# Main_Flam.net
KiCad netlist of a schematic drawn in EAGLE
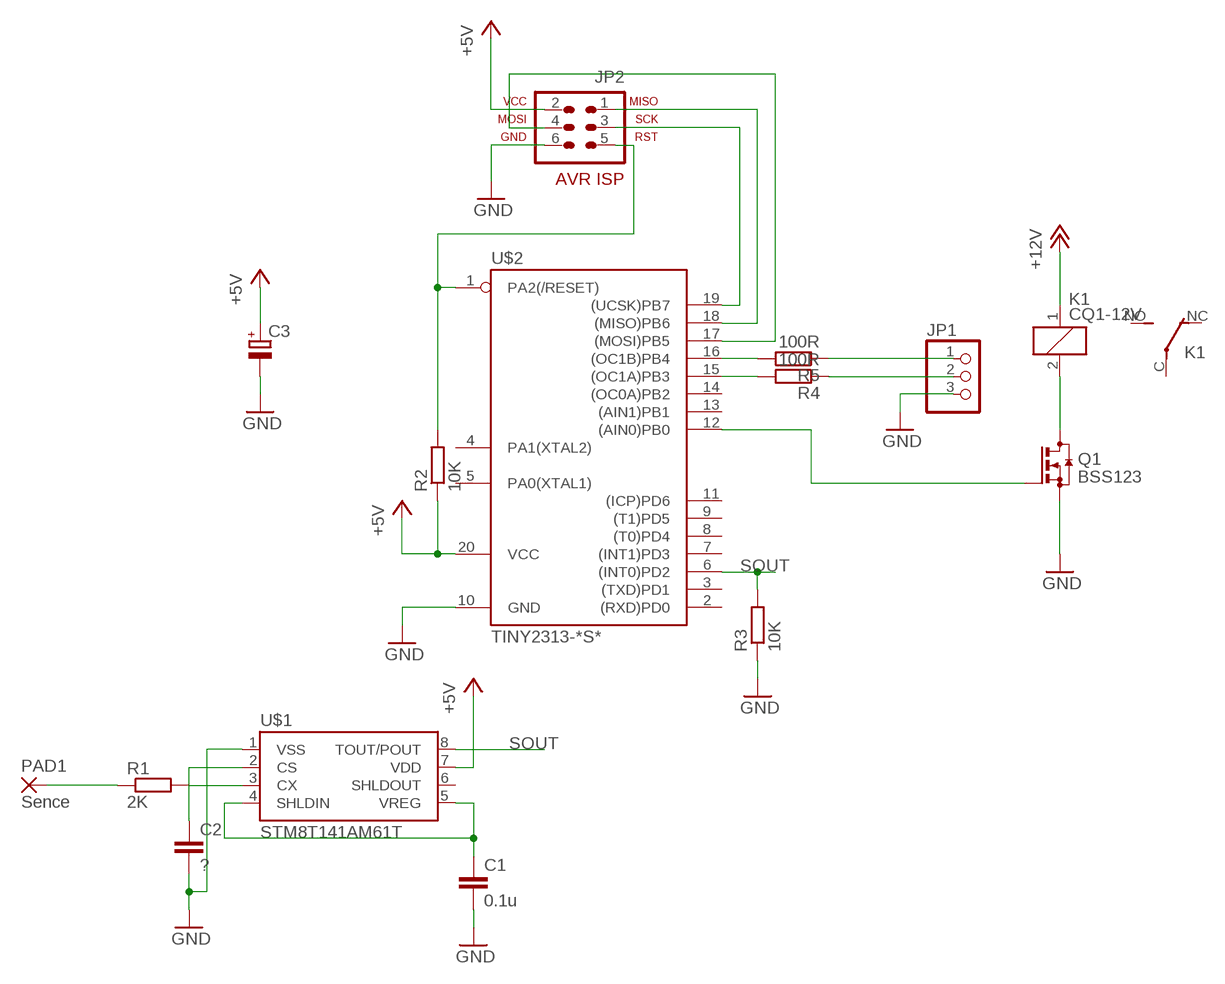
[diagram p0: schematic, sheet 1]

(export (version "E")
  (design (tool "Eeschema 10.0.6"))
  (components
    (comp (ref "C1")
      (value "0.1u")
      (footprint "eagle-import:C1206")
      (libsource (lib "eagle-import") (part "C-EUC1206"))
    )
    (comp (ref "C2")
      (value "?")
      (footprint "eagle-import:C1206")
      (libsource (lib "eagle-import") (part "C-EUC1206"))
    )
    (comp (ref "C3")
      (value "CPOL-EUSMCB")
      (footprint "eagle-import:SMC_B")
      (libsource (lib "eagle-import") (part "CPOL-EUSMCB"))
    )
    (comp (ref "JP1")
      (value "PINHD-1X3")
      (footprint "eagle-import:1X03")
      (libsource (lib "eagle-import") (part "PINHD-1X3"))
    )
    (comp (ref "JP2")
      (value "AVR-ISP-6VERT")
      (footprint "eagle-import:AVR-ISP-6")
      (libsource (lib "eagle-import") (part "AVR-ISP-6VERT"))
    )
    (comp (ref "K1")
      (value "CQ1-12V")
      (footprint "eagle-import:CQ1")
      (libsource (lib "eagle-import") (part "CQ1-12V"))
    )
    (comp (ref "PAD1")
      (value "Sence")
      (footprint "eagle-import:2,54_0,8")
      (libsource (lib "eagle-import") (part "2,54/0,8"))
    )
    (comp (ref "Q1")
      (value "BSS123")
      (footprint "eagle-import:SOT23")
      (libsource (lib "eagle-import") (part "BSS123"))
    )
    (comp (ref "R1")
      (value "2K")
      (footprint "eagle-import:R1206")
      (libsource (lib "eagle-import") (part "R-EU_R1206"))
    )
    (comp (ref "R2")
      (value "10K")
      (footprint "eagle-import:R1206")
      (libsource (lib "eagle-import") (part "R-EU_R1206"))
    )
    (comp (ref "R3")
      (value "10K")
      (footprint "eagle-import:R1206")
      (libsource (lib "eagle-import") (part "R-EU_R1206"))
    )
    (comp (ref "R4")
      (value "100R")
      (footprint "eagle-import:R1206")
      (libsource (lib "eagle-import") (part "R-EU_R1206"))
    )
    (comp (ref "R5")
      (value "100R")
      (footprint "eagle-import:R1206")
      (libsource (lib "eagle-import") (part "R-EU_R1206"))
    )
    (comp (ref "U$1")
      (value "STM8T141AM61T")
      (footprint "eagle-import:SO8")
      (libsource (lib "eagle-import") (part "STM8T141AM61T"))
    )
    (comp (ref "U$2")
      (value "TINY2313-*S*")
      (footprint "eagle-import:SO20L$")
      (libsource (lib "eagle-import") (part "TINY2313-S"))
    )
  )
  (nets
    (net (code "1") (name "+5V") (class "Default")
      (node (ref "C3") (pin "+") (pinfunction "+_+") (pintype "passive"))
      (node (ref "JP2") (pin "2") (pinfunction "2_2") (pintype "passive"))
      (node (ref "R2") (pin "1") (pinfunction "1_1") (pintype "passive"))
      (node (ref "U$1") (pin "7") (pinfunction "VDD_7") (pintype "bidirectional"))
      (node (ref "U$2") (pin "20") (pinfunction "VCC_20") (pintype "power_in"))
    )
    (net (code "2") (name "+12V") (class "Default")
      (node (ref "K1") (pin "1") (pinfunction "1_1") (pintype "passive"))
    )
    (net (code "3") (name "/SOUT") (class "Default")
      (node (ref "R3") (pin "2") (pinfunction "2_2") (pintype "passive"))
      (node (ref "U$1") (pin "8") (pinfunction "TOUT/POUT_8") (pintype "bidirectional"))
      (node (ref "U$2") (pin "6") (pinfunction "(INT0)PD2_6") (pintype "bidirectional"))
    )
    (net (code "4") (name "GND") (class "Default")
      (node (ref "C1") (pin "2") (pinfunction "2_2") (pintype "passive"))
      (node (ref "C2") (pin "2") (pinfunction "2_2") (pintype "passive"))
      (node (ref "C3") (pin "-") (pinfunction "-_-") (pintype "passive"))
      (node (ref "JP1") (pin "3") (pinfunction "3_3") (pintype "passive"))
      (node (ref "JP2") (pin "6") (pinfunction "6_6") (pintype "passive"))
      (node (ref "Q1") (pin "2") (pinfunction "S_2") (pintype "passive"))
      (node (ref "R3") (pin "1") (pinfunction "1_1") (pintype "passive"))
      (node (ref "U$1") (pin "1") (pinfunction "VSS_1") (pintype "bidirectional"))
      (node (ref "U$2") (pin "10") (pinfunction "GND_10") (pintype "power_in"))
    )
    (net (code "5") (name "Net-(JP1-Pad1)") (class "Default")
      (node (ref "JP1") (pin "1") (pinfunction "1_1") (pintype "passive"))
      (node (ref "R5") (pin "1") (pinfunction "1_1") (pintype "passive"))
    )
    (net (code "6") (name "Net-(JP1-Pad2)") (class "Default")
      (node (ref "JP1") (pin "2") (pinfunction "2_2") (pintype "passive"))
      (node (ref "R4") (pin "1") (pinfunction "1_1") (pintype "passive"))
    )
    (net (code "7") (name "Net-(PAD1-P)") (class "Default")
      (node (ref "PAD1") (pin "1") (pinfunction "P_1") (pintype "passive"))
      (node (ref "R1") (pin "1") (pinfunction "1_1") (pintype "passive"))
    )
    (net (code "8") (name "Net-(Q1-D)") (class "Default")
      (node (ref "K1") (pin "2") (pinfunction "2_2") (pintype "passive"))
      (node (ref "Q1") (pin "3") (pinfunction "D_3") (pintype "passive"))
    )
    (net (code "9") (name "Net-(Q1-G)") (class "Default")
      (node (ref "Q1") (pin "1") (pinfunction "G_1") (pintype "passive"))
      (node (ref "U$2") (pin "12") (pinfunction "(AIN0)PB0_12") (pintype "bidirectional"))
    )
    (net (code "10") (name "Net-(U$1-CS)") (class "Default")
      (node (ref "C2") (pin "1") (pinfunction "1_1") (pintype "passive"))
      (node (ref "U$1") (pin "2") (pinfunction "CS_2") (pintype "bidirectional"))
    )
    (net (code "11") (name "Net-(U$1-CX)") (class "Default")
      (node (ref "R1") (pin "2") (pinfunction "2_2") (pintype "passive"))
      (node (ref "U$1") (pin "3") (pinfunction "CX_3") (pintype "bidirectional"))
    )
    (net (code "12") (name "Net-(U$1-SHLDIN)") (class "Default")
      (node (ref "C1") (pin "1") (pinfunction "1_1") (pintype "passive"))
      (node (ref "U$1") (pin "4") (pinfunction "SHLDIN_4") (pintype "bidirectional"))
      (node (ref "U$1") (pin "5") (pinfunction "VREG_5") (pintype "bidirectional"))
    )
    (net (code "13") (name "Net-(U$2-(MISO)PB6)") (class "Default")
      (node (ref "JP2") (pin "1") (pinfunction "1_1") (pintype "passive"))
      (node (ref "U$2") (pin "18") (pinfunction "(MISO)PB6_18") (pintype "bidirectional"))
    )
    (net (code "14") (name "Net-(U$2-(MOSI)PB5)") (class "Default")
      (node (ref "JP2") (pin "4") (pinfunction "4_4") (pintype "passive"))
      (node (ref "U$2") (pin "17") (pinfunction "(MOSI)PB5_17") (pintype "bidirectional"))
    )
    (net (code "15") (name "Net-(U$2-(OC1A)PB3)") (class "Default")
      (node (ref "R4") (pin "2") (pinfunction "2_2") (pintype "passive"))
      (node (ref "U$2") (pin "15") (pinfunction "(OC1A)PB3_15") (pintype "bidirectional"))
    )
    (net (code "16") (name "Net-(U$2-(OC1B)PB4)") (class "Default")
      (node (ref "R5") (pin "2") (pinfunction "2_2") (pintype "passive"))
      (node (ref "U$2") (pin "16") (pinfunction "(OC1B)PB4_16") (pintype "bidirectional"))
    )
    (net (code "17") (name "Net-(U$2-(UCSK)PB7)") (class "Default")
      (node (ref "JP2") (pin "3") (pinfunction "3_3") (pintype "passive"))
      (node (ref "U$2") (pin "19") (pinfunction "(UCSK)PB7_19") (pintype "bidirectional"))
    )
    (net (code "18") (name "Net-(U$2-PA2({slash}RESET))") (class "Default")
      (node (ref "JP2") (pin "5") (pinfunction "5_5") (pintype "passive"))
      (node (ref "R2") (pin "2") (pinfunction "2_2") (pintype "passive"))
      (node (ref "U$2") (pin "1") (pinfunction "PA2(/RESET)_1") (pintype "input"))
    )
    (net (code "19") (name "unconnected-(K1B-O-PadNC)") (class "Default")
      (node (ref "K1") (pin "NC") (pinfunction "O_NC") (pintype "passive"))
    )
    (net (code "20") (name "unconnected-(K1B-P-PadC)") (class "Default")
      (node (ref "K1") (pin "C") (pinfunction "P_C") (pintype "passive"))
    )
    (net (code "21") (name "unconnected-(K1B-S-PadNO)") (class "Default")
      (node (ref "K1") (pin "NO") (pinfunction "S_NO") (pintype "passive"))
    )
    (net (code "22") (name "unconnected-(U$1-SHLDOUT-Pad6)") (class "Default")
      (node (ref "U$1") (pin "6") (pinfunction "SHLDOUT_6") (pintype "bidirectional"))
    )
    (net (code "23") (name "unconnected-(U$2-(AIN1)PB1-Pad13)") (class "Default")
      (node (ref "U$2") (pin "13") (pinfunction "(AIN1)PB1_13") (pintype "bidirectional"))
    )
    (net (code "24") (name "unconnected-(U$2-(ICP)PD6-Pad11)") (class "Default")
      (node (ref "U$2") (pin "11") (pinfunction "(ICP)PD6_11") (pintype "bidirectional"))
    )
    (net (code "25") (name "unconnected-(U$2-(INT1)PD3-Pad7)") (class "Default")
      (node (ref "U$2") (pin "7") (pinfunction "(INT1)PD3_7") (pintype "bidirectional"))
    )
    (net (code "26") (name "unconnected-(U$2-(OC0A)PB2-Pad14)") (class "Default")
      (node (ref "U$2") (pin "14") (pinfunction "(OC0A)PB2_14") (pintype "bidirectional"))
    )
    (net (code "27") (name "unconnected-(U$2-(RXD)PD0-Pad2)") (class "Default")
      (node (ref "U$2") (pin "2") (pinfunction "(RXD)PD0_2") (pintype "bidirectional"))
    )
    (net (code "28") (name "unconnected-(U$2-(T0)PD4-Pad8)") (class "Default")
      (node (ref "U$2") (pin "8") (pinfunction "(T0)PD4_8") (pintype "bidirectional"))
    )
    (net (code "29") (name "unconnected-(U$2-(T1)PD5-Pad9)") (class "Default")
      (node (ref "U$2") (pin "9") (pinfunction "(T1)PD5_9") (pintype "bidirectional"))
    )
    (net (code "30") (name "unconnected-(U$2-(TXD)PD1-Pad3)") (class "Default")
      (node (ref "U$2") (pin "3") (pinfunction "(TXD)PD1_3") (pintype "bidirectional"))
    )
    (net (code "31") (name "unconnected-(U$2-PA0(XTAL1)-Pad5)") (class "Default")
      (node (ref "U$2") (pin "5") (pinfunction "PA0(XTAL1)_5") (pintype "bidirectional"))
    )
    (net (code "32") (name "unconnected-(U$2-PA1(XTAL2)-Pad4)") (class "Default")
      (node (ref "U$2") (pin "4") (pinfunction "PA1(XTAL2)_4") (pintype "bidirectional"))
    )
  )
)
